# Cyusb3014_-_3.net
KiCad netlist of a schematic drawn in Altium Designer
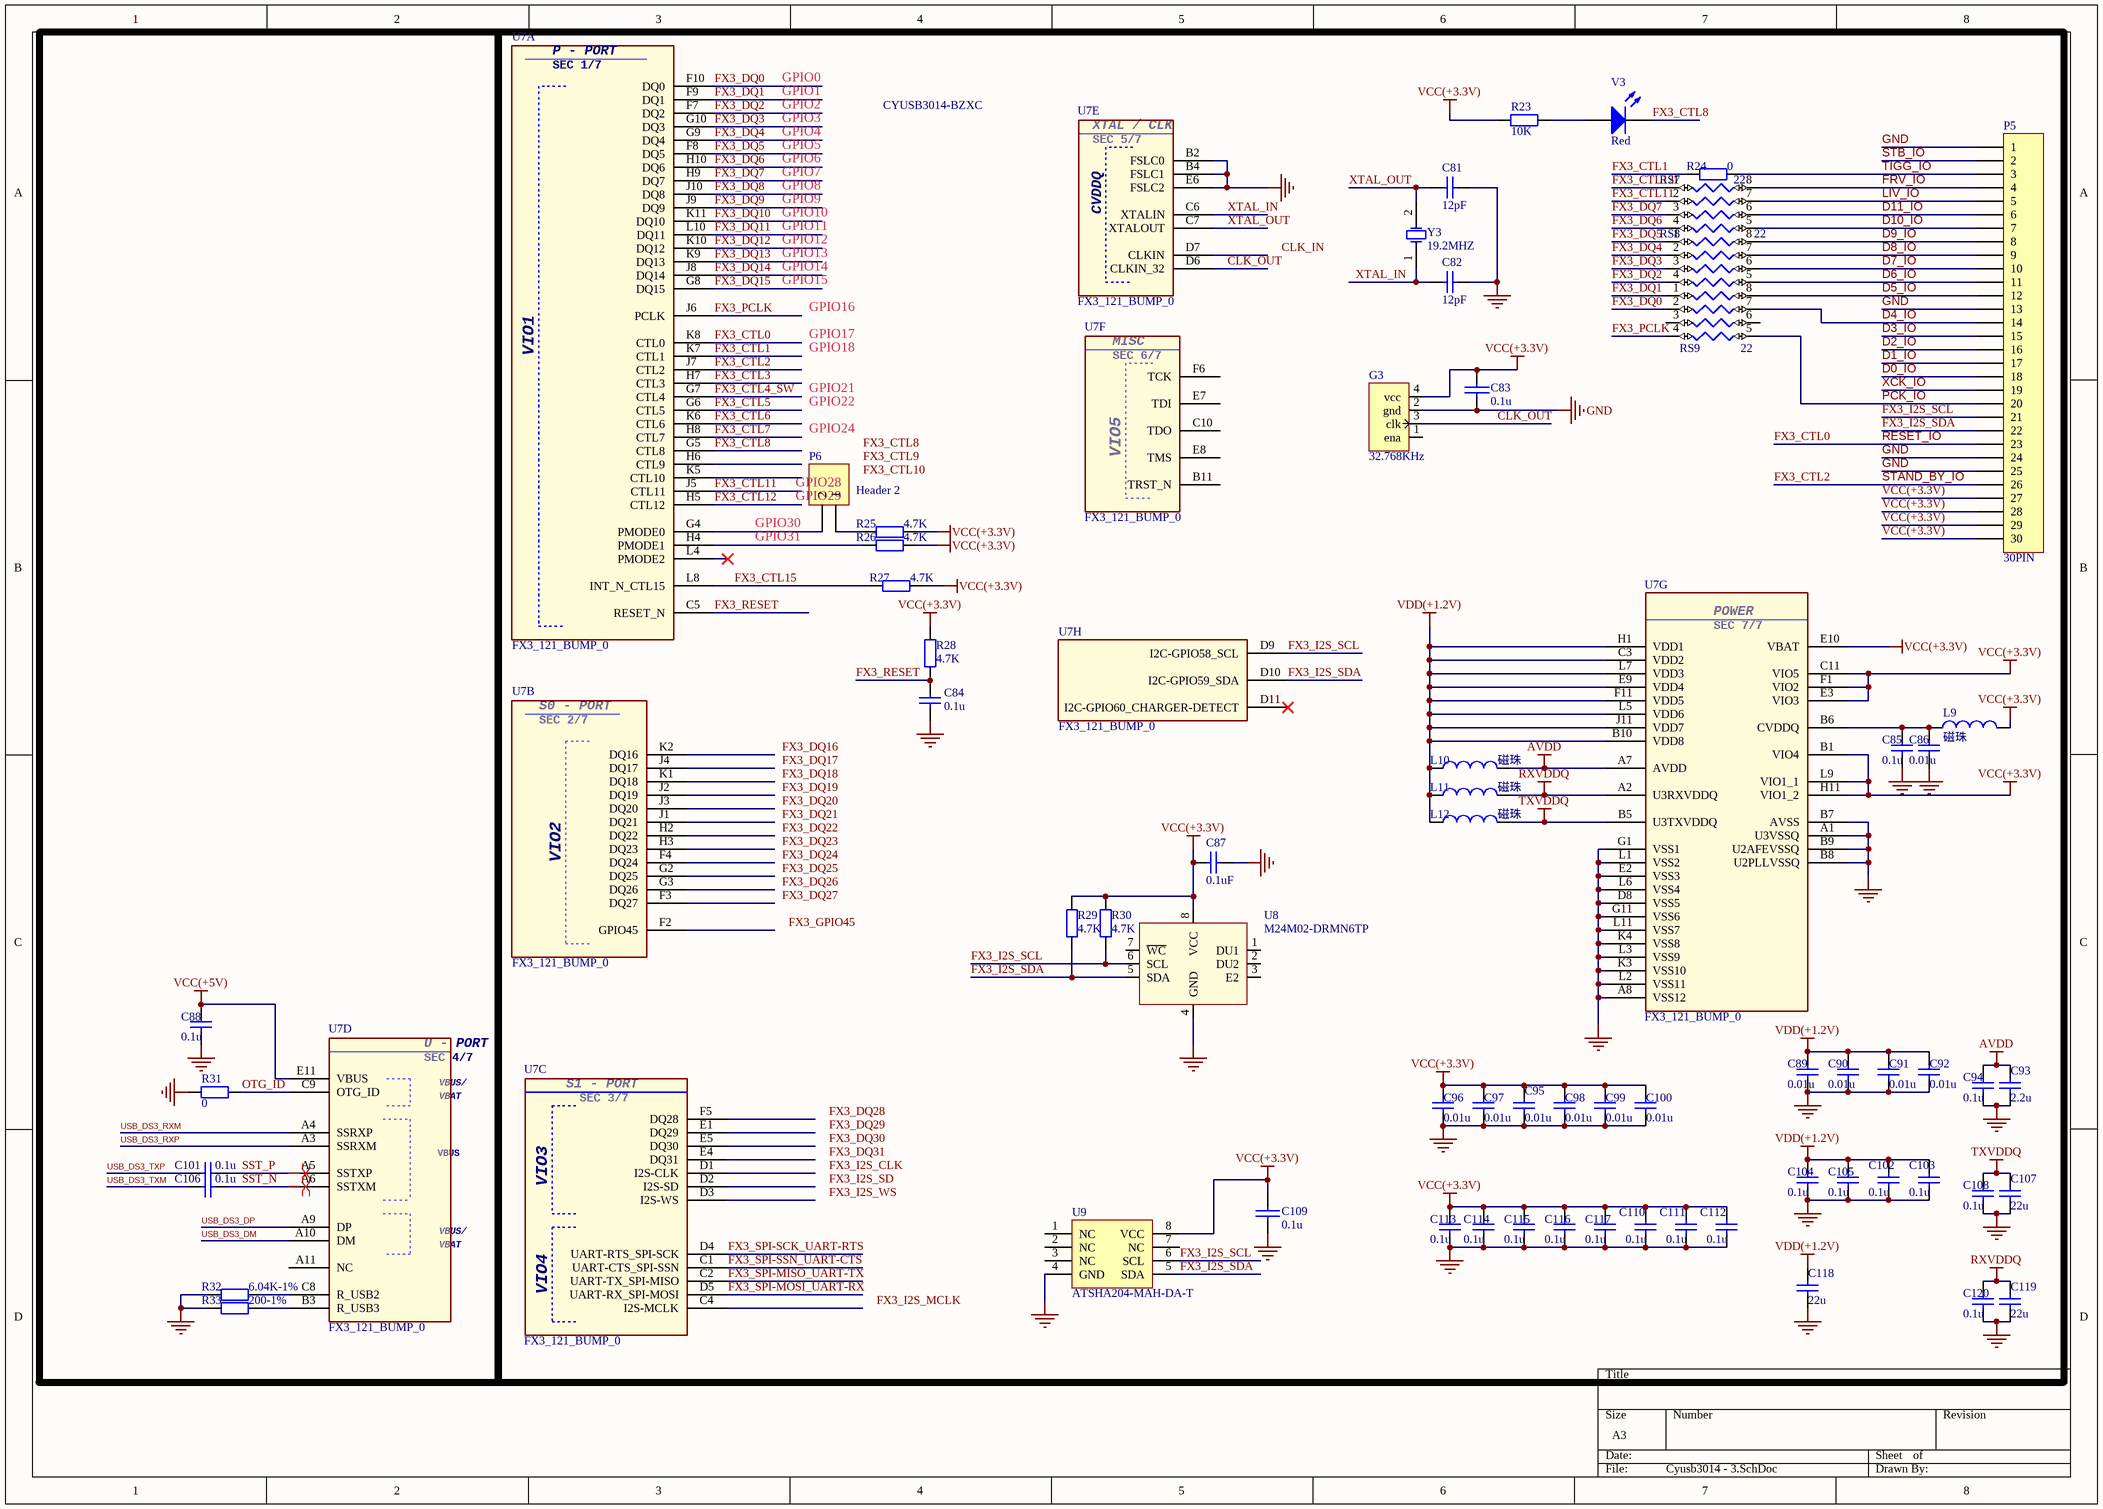
[diagram p0: Cyusb3014 - 3.SchDoc]

(export (version "E")
  (design (tool "Eeschema 10.0.6"))
  (components
    (comp (ref "C81")
      (value "12pF")
      (footprint "0603S-CAP")
      (description "CAP CER SMT 4.3pF 0805")
      (fields
        (field (name "2. MANUFACTURERE PART NUMBER") "C0805C439D5GACTU")
        (field (name "8. ALTERNATE PART") "any")
      )
      (libsource (lib "Peeple_eval") (part "CAP CER SMT 4.3pF 0805"))
    )
    (comp (ref "C82")
      (value "12pF")
      (footprint "0603S-CAP")
      (description "CAP CER SMT 4.3pF 0805")
      (fields
        (field (name "2. MANUFACTURERE PART NUMBER") "C0805C439D5GACTU")
        (field (name "8. ALTERNATE PART") "any")
      )
      (libsource (lib "Peeple_eval") (part "CAP CER SMT 4.3pF 0805"))
    )
    (comp (ref "C83")
      (value "0.1u")
      (footprint "0603S-CAP")
      (description "RC=1206")
      (libsource (lib "*") (part "CAP"))
    )
    (comp (ref "C84")
      (value "0.1u")
      (footprint "0603S-CAP")
      (description "50V/8.2u/0805")
      (fields (field (name "PUBLISHER") "Altium Limited"))
      (libsource (lib "Miscellaneous Devices") (part "Cap"))
    )
    (comp (ref "C85")
      (value "0.1u")
      (footprint "C0402")
      (description "Capacitor")
      (fields (field (name "PUBLISHER") "Altium Limited"))
      (libsource (lib "WM360") (part "CAP0805"))
    )
    (comp (ref "C86")
      (value "0.01u")
      (footprint "C0402")
      (description "Capacitor")
      (fields (field (name "PUBLISHER") "Altium Limited"))
      (libsource (lib "WM360") (part "CAP0805"))
    )
    (comp (ref "C87")
      (value "0.1uF")
      (footprint "0603S-CAP")
      (description "CAP SMT 0.1uF 16V X7R")
      (fields
        (field (name "2. MANUFACTURERE PART NUMBER") "C0805C104K4RACTU")
        (field (name "8. ALTERNATE PART") "any")
      )
      (libsource (lib "Peeple_eval") (part "CAP SMT 0.1uF 16V X7R"))
    )
    (comp (ref "C88")
      (value "0.1u")
      (footprint "C0402")
      (description "Capacitor")
      (fields (field (name "PUBLISHER") "Altium Limited"))
      (libsource (lib "WM360") (part "CAP0805"))
    )
    (comp (ref "C89")
      (value "0.01u")
      (footprint "C0402")
      (description "Capacitor")
      (fields (field (name "PUBLISHER") "Altium Limited"))
      (libsource (lib "WM360") (part "CAP0805"))
    )
    (comp (ref "C90")
      (value "0.01u")
      (footprint "C0402")
      (description "Capacitor")
      (fields (field (name "PUBLISHER") "Altium Limited"))
      (libsource (lib "WM360") (part "CAP0805"))
    )
    (comp (ref "C91")
      (value "0.01u")
      (footprint "C0402")
      (description "Capacitor")
      (fields (field (name "PUBLISHER") "Altium Limited"))
      (libsource (lib "WM360") (part "CAP0805"))
    )
    (comp (ref "C92")
      (value "0.01u")
      (footprint "C0402")
      (description "Capacitor")
      (fields (field (name "PUBLISHER") "Altium Limited"))
      (libsource (lib "WM360") (part "CAP0805"))
    )
    (comp (ref "C93")
      (value "2.2u")
      (footprint "C0805S-CAP")
      (description "Capacitor")
      (fields (field (name "PUBLISHER") "Altium Limited"))
      (libsource (lib "USB_CAMERA") (part "CAP0805"))
    )
    (comp (ref "C94")
      (value "0.1u")
      (footprint "C0402")
      (description "Capacitor")
      (fields (field (name "PUBLISHER") "Altium Limited"))
      (libsource (lib "WM360") (part "CAP0805"))
    )
    (comp (ref "C95")
      (value "0.01u")
      (footprint "C0402")
      (description "Capacitor")
      (fields (field (name "PUBLISHER") "Altium Limited"))
      (libsource (lib "WM360") (part "CAP0805"))
    )
    (comp (ref "C96")
      (value "0.01u")
      (footprint "C0402")
      (description "Capacitor")
      (fields (field (name "PUBLISHER") "Altium Limited"))
      (libsource (lib "WM360") (part "CAP0805"))
    )
    (comp (ref "C97")
      (value "0.01u")
      (footprint "C0402")
      (description "Capacitor")
      (fields (field (name "PUBLISHER") "Altium Limited"))
      (libsource (lib "WM360") (part "CAP0805"))
    )
    (comp (ref "C98")
      (value "0.01u")
      (footprint "C0402")
      (description "Capacitor")
      (fields (field (name "PUBLISHER") "Altium Limited"))
      (libsource (lib "WM360") (part "CAP0805"))
    )
    (comp (ref "C99")
      (value "0.01u")
      (footprint "C0402")
      (description "Capacitor")
      (fields (field (name "PUBLISHER") "Altium Limited"))
      (libsource (lib "WM360") (part "CAP0805"))
    )
    (comp (ref "C100")
      (value "0.01u")
      (footprint "C0402")
      (description "Capacitor")
      (fields (field (name "PUBLISHER") "Altium Limited"))
      (libsource (lib "WM360") (part "CAP0805"))
    )
    (comp (ref "C101")
      (value "0.1u")
      (footprint "C0402")
      (description "Capacitor")
      (fields (field (name "PUBLISHER") "Altium Limited"))
      (libsource (lib "WM360") (part "CAP0805"))
    )
    (comp (ref "C102")
      (value "0.1u")
      (footprint "C0402")
      (description "Capacitor")
      (fields (field (name "PUBLISHER") "Altium Limited"))
      (libsource (lib "WM360") (part "CAP0805"))
    )
    (comp (ref "C103")
      (value "0.1u")
      (footprint "C0402")
      (description "Capacitor")
      (fields (field (name "PUBLISHER") "Altium Limited"))
      (libsource (lib "WM360") (part "CAP0805"))
    )
    (comp (ref "C104")
      (value "0.1u")
      (footprint "C0402")
      (description "Capacitor")
      (fields (field (name "PUBLISHER") "Altium Limited"))
      (libsource (lib "WM360") (part "CAP0805"))
    )
    (comp (ref "C105")
      (value "0.1u")
      (footprint "C0402")
      (description "Capacitor")
      (fields (field (name "PUBLISHER") "Altium Limited"))
      (libsource (lib "WM360") (part "CAP0805"))
    )
    (comp (ref "C106")
      (value "0.1u")
      (footprint "C0402")
      (description "Capacitor")
      (fields (field (name "PUBLISHER") "Altium Limited"))
      (libsource (lib "WM360") (part "CAP0805"))
    )
    (comp (ref "C107")
      (value "22u")
      (footprint "C0805S-CAP")
      (description "Capacitor")
      (fields (field (name "PUBLISHER") "Altium Limited"))
      (libsource (lib "USB_CAMERA") (part "CAP0805"))
    )
    (comp (ref "C108")
      (value "0.1u")
      (footprint "C0402")
      (description "Capacitor")
      (fields (field (name "PUBLISHER") "Altium Limited"))
      (libsource (lib "WM360") (part "CAP0805"))
    )
    (comp (ref "C109")
      (value "0.1u")
      (footprint "0603S-CAP")
      (description "RC=1206")
      (libsource (lib "*") (part "CAP"))
    )
    (comp (ref "C110")
      (value "0.1u")
      (footprint "C0402")
      (description "Capacitor")
      (fields (field (name "PUBLISHER") "Altium Limited"))
      (libsource (lib "WM360") (part "CAP0805"))
    )
    (comp (ref "C111")
      (value "0.1u")
      (footprint "C0402")
      (description "Capacitor")
      (fields (field (name "PUBLISHER") "Altium Limited"))
      (libsource (lib "WM360") (part "CAP0805"))
    )
    (comp (ref "C112")
      (value "0.1u")
      (footprint "C0402")
      (description "Capacitor")
      (fields (field (name "PUBLISHER") "Altium Limited"))
      (libsource (lib "WM360") (part "CAP0805"))
    )
    (comp (ref "C113")
      (value "0.1u")
      (footprint "C0402")
      (description "Capacitor")
      (fields (field (name "PUBLISHER") "Altium Limited"))
      (libsource (lib "WM360") (part "CAP0805"))
    )
    (comp (ref "C114")
      (value "0.1u")
      (footprint "C0402")
      (description "Capacitor")
      (fields (field (name "PUBLISHER") "Altium Limited"))
      (libsource (lib "WM360") (part "CAP0805"))
    )
    (comp (ref "C115")
      (value "0.1u")
      (footprint "C0402")
      (description "Capacitor")
      (fields (field (name "PUBLISHER") "Altium Limited"))
      (libsource (lib "WM360") (part "CAP0805"))
    )
    (comp (ref "C116")
      (value "0.1u")
      (footprint "C0402")
      (description "Capacitor")
      (fields (field (name "PUBLISHER") "Altium Limited"))
      (libsource (lib "WM360") (part "CAP0805"))
    )
    (comp (ref "C117")
      (value "0.1u")
      (footprint "C0402")
      (description "Capacitor")
      (fields (field (name "PUBLISHER") "Altium Limited"))
      (libsource (lib "WM360") (part "CAP0805"))
    )
    (comp (ref "C118")
      (value "22u")
      (footprint "C0805S-CAP")
      (description "Capacitor")
      (fields (field (name "PUBLISHER") "Altium Limited"))
      (libsource (lib "USB_CAMERA") (part "CAP0805"))
    )
    (comp (ref "C119")
      (value "22u")
      (footprint "C0805S-CAP")
      (description "Capacitor")
      (fields (field (name "PUBLISHER") "Altium Limited"))
      (libsource (lib "USB_CAMERA") (part "CAP0805"))
    )
    (comp (ref "C120")
      (value "0.1u")
      (footprint "C0402")
      (description "Capacitor")
      (fields (field (name "PUBLISHER") "Altium Limited"))
      (libsource (lib "WM360") (part "CAP0805"))
    )
    (comp (ref "G3") (value "32.768KHz") (footprint "爱普生晶振3.2×2.5mm") (libsource (lib "*") (part "CTY4-B")))
    (comp (ref "L9")
      (value "磁珠")
      (footprint "L0603")
      (description "Inductor")
      (fields (field (name "PUBLISHER") "Altium Limited"))
      (libsource (lib "Miscellaneous Devices") (part "Inductor"))
    )
    (comp (ref "L10")
      (value "磁珠")
      (footprint "L0603")
      (description "Inductor")
      (fields (field (name "PUBLISHER") "Altium Limited"))
      (libsource (lib "Miscellaneous Devices") (part "Inductor"))
    )
    (comp (ref "L11")
      (value "磁珠")
      (footprint "L0603")
      (description "Inductor")
      (fields (field (name "PUBLISHER") "Altium Limited"))
      (libsource (lib "Miscellaneous Devices") (part "Inductor"))
    )
    (comp (ref "L12")
      (value "磁珠")
      (footprint "L0603")
      (description "Inductor")
      (fields (field (name "PUBLISHER") "Altium Limited"))
      (libsource (lib "Miscellaneous Devices") (part "Inductor"))
    )
    (comp (ref "P5")
      (value "30PIN")
      (footprint "FH12-30S-0.5SH")
      (description "Header, 30-Pin")
      (fields (field (name "PUBLISHER") "Altium Limited"))
      (libsource (lib "Miscellaneous Connectors") (part "Header 30"))
    )
    (comp (ref "P6")
      (value "Header 2")
      (footprint "HDR1X2")
      (description "Header, 2-Pin")
      (fields (field (name "PUBLISHER") "Altium Limited"))
      (libsource (lib "Miscellaneous Connectors") (part "Header 2"))
    )
    (comp (ref "R23")
      (value "10K")
      (footprint "0603S-RES")
      (description "Resistor")
      (fields (field (name "PUBLISHER") "Altium Limited"))
      (libsource (lib "") (part "Res2_2"))
    )
    (comp (ref "R24")
      (value "0")
      (footprint "0603S-RES")
      (description "Resistor")
      (fields (field (name "PUBLISHER") "Altium Limited"))
      (libsource (lib "") (part "Res2_2"))
    )
    (comp (ref "R25")
      (value "4.7K")
      (footprint "0603S-RES")
      (description "Resistor")
      (fields (field (name "PUBLISHER") "Altium Limited"))
      (libsource (lib "DM642") (part "Res2"))
    )
    (comp (ref "R26")
      (value "4.7K")
      (footprint "0603S-RES")
      (description "Resistor")
      (fields (field (name "PUBLISHER") "Altium Limited"))
      (libsource (lib "DM642") (part "Res2"))
    )
    (comp (ref "R27")
      (value "4.7K")
      (footprint "0603S-RES")
      (description "Resistor")
      (fields (field (name "PUBLISHER") "Altium Limited"))
      (libsource (lib "") (part "Res2_1"))
    )
    (comp (ref "R28")
      (value "4.7K")
      (footprint "0603S-RES")
      (description "Resistor")
      (fields (field (name "PUBLISHER") "Altium Limited"))
      (libsource (lib "") (part "Res2_3"))
    )
    (comp (ref "R29")
      (value "4.7K")
      (footprint "0603S-RES")
      (description "Resistor")
      (fields (field (name "PUBLISHER") "Altium Limited"))
      (libsource (lib "DM642") (part "Res2"))
    )
    (comp (ref "R30")
      (value "4.7K")
      (footprint "0603S-RES")
      (description "Resistor")
      (fields (field (name "PUBLISHER") "Altium Limited"))
      (libsource (lib "DM642") (part "Res2"))
    )
    (comp (ref "R31")
      (value "0")
      (footprint "0603S-RES")
      (description "Resistor")
      (fields (field (name "PUBLISHER") "Altium Limited"))
      (libsource (lib "") (part "Res2_1"))
    )
    (comp (ref "R32")
      (value "6.04K-1%")
      (footprint "0603S-RES")
      (description "Resistor")
      (fields (field (name "PUBLISHER") "Altium Limited"))
      (libsource (lib "") (part "Res2_1"))
    )
    (comp (ref "R33")
      (value "200-1%")
      (footprint "0603S-RES")
      (description "Resistor")
      (fields (field (name "PUBLISHER") "Altium Limited"))
      (libsource (lib "") (part "Res2_1"))
    )
    (comp (ref "RS7") (value "22") (footprint "NC06-4") (libsource (lib "*") (part "RN4")))
    (comp (ref "RS8") (value "22") (footprint "NC06-4") (libsource (lib "*") (part "RN4")))
    (comp (ref "RS9") (value "22") (footprint "NC06-4") (libsource (lib "*") (part "RN4")))
    (comp (ref "U7")
      (value "FX3_121_BUMP_0")
      (footprint "121_BGA_FX3")
      (libsource (lib "USB_CAMERA") (part "FX3_121_BUMP_0"))
    )
    (comp (ref "U8")
      (value "M24M02-DRMN6TP")
      (footprint "SOIC127P600X175-8N")
      (description "IC EEPROM 64KBIT 400KHZ 8SOIC")
      (fields
        (field (name "MANUFACTURER") "Microchip Technology")
        (field (name "MANUFACTURER PART NUMBER") "24LC64-I/SN")
      )
      (libsource (lib "Schlib1") (part "24LC64-I/SN"))
    )
    (comp (ref "U9")
      (value "ATSHA204-MAH-DA-T")
      (footprint "UDFN")
      (libsource (lib "CY7C68013-56") (part "AT24C128"))
    )
    (comp (ref "V3")
      (value "Red")
      (footprint "LED0805S")
      (description "Typical INFRARED GaAs LED")
      (fields (field (name "PUBLISHER") "Altium Limited"))
      (libsource (lib "DM642") (part "LED0"))
    )
    (comp (ref "Y3")
      (value "19.2MHZ")
      (footprint "爱普生晶振3.2×2.5MM - 无源")
      (description "Crystal, CRYSTAL 32.768KHZ 6PF SMD")
      (fields
        (field (name "2. MANUFACTURERE PART NUMBER") "ABS07-120-32.768KHZ-T")
        (field (name "4. SUPPLIER PART NUMBER") "535-11937-1-ND")
      )
      (libsource (lib "Peeple_eval") (part "XTAL 32.768KHZ"))
    )
  )
  (nets
    (net (code "2") (name "/CLK_OUT") (class "Default")
      (node (ref "G3") (pin "3") (pinfunction "clk_3") (pintype "passive"))
      (node (ref "U7") (pin "D6") (pinfunction "CLKIN_32_D6") (pintype "passive"))
    )
    (net (code "3") (name "/D0_IO") (class "Default")
      (node (ref "P5") (pin "18") (pinfunction "18_18") (pintype "passive"))
    )
    (net (code "4") (name "/D1_IO") (class "Default")
      (node (ref "P5") (pin "17") (pinfunction "17_17") (pintype "passive"))
    )
    (net (code "5") (name "/D2_IO") (class "Default")
      (node (ref "P5") (pin "16") (pinfunction "16_16") (pintype "passive"))
    )
    (net (code "6") (name "/D3_IO") (class "Default")
      (node (ref "P5") (pin "15") (pinfunction "15_15") (pintype "passive"))
    )
    (net (code "7") (name "/D4_IO") (class "Default")
      (node (ref "P5") (pin "14") (pinfunction "14_14") (pintype "passive"))
      (node (ref "RS9") (pin "7") (pinfunction "7_7") (pintype "bidirectional"))
    )
    (net (code "8") (name "/D5_IO") (class "Default")
      (node (ref "P5") (pin "12") (pinfunction "12_12") (pintype "passive"))
      (node (ref "RS9") (pin "8") (pinfunction "8_8") (pintype "bidirectional"))
    )
    (net (code "9") (name "/D6_IO") (class "Default")
      (node (ref "P5") (pin "11") (pinfunction "11_11") (pintype "passive"))
      (node (ref "RS8") (pin "5") (pinfunction "5_5") (pintype "bidirectional"))
    )
    (net (code "10") (name "/D7_IO") (class "Default")
      (node (ref "P5") (pin "10") (pinfunction "10_10") (pintype "passive"))
      (node (ref "RS8") (pin "6") (pinfunction "6_6") (pintype "bidirectional"))
    )
    (net (code "11") (name "/D8_IO") (class "Default")
      (node (ref "P5") (pin "9") (pinfunction "9_9") (pintype "passive"))
      (node (ref "RS8") (pin "7") (pinfunction "7_7") (pintype "bidirectional"))
    )
    (net (code "12") (name "/D9_IO") (class "Default")
      (node (ref "P5") (pin "8") (pinfunction "8_8") (pintype "passive"))
      (node (ref "RS8") (pin "8") (pinfunction "8_8") (pintype "bidirectional"))
    )
    (net (code "13") (name "/D10_IO") (class "Default")
      (node (ref "P5") (pin "7") (pinfunction "7_7") (pintype "passive"))
      (node (ref "RS7") (pin "5") (pinfunction "5_5") (pintype "bidirectional"))
    )
    (net (code "14") (name "/D11_IO") (class "Default")
      (node (ref "P5") (pin "6") (pinfunction "6_6") (pintype "passive"))
      (node (ref "RS7") (pin "6") (pinfunction "6_6") (pintype "bidirectional"))
    )
    (net (code "15") (name "/FRV_IO") (class "Default")
      (node (ref "P5") (pin "4") (pinfunction "4_4") (pintype "passive"))
      (node (ref "RS7") (pin "8") (pinfunction "8_8") (pintype "bidirectional"))
    )
    (net (code "16") (name "/FX3_CTL0") (class "Default")
      (node (ref "P5") (pin "23") (pinfunction "23_23") (pintype "passive"))
      (node (ref "U7") (pin "K8") (pinfunction "CTL0_K8") (pintype "passive"))
    )
    (net (code "17") (name "/FX3_CTL1") (class "Default")
      (node (ref "R24") (pin "2") (pinfunction "2_2") (pintype "passive"))
      (node (ref "U7") (pin "K7") (pinfunction "CTL1_K7") (pintype "passive"))
    )
    (net (code "18") (name "/FX3_CTL2") (class "Default")
      (node (ref "P5") (pin "26") (pinfunction "26_26") (pintype "passive"))
      (node (ref "U7") (pin "J7") (pinfunction "CTL2_J7") (pintype "passive"))
    )
    (net (code "19") (name "/FX3_CTL3") (class "Default")
      (node (ref "U7") (pin "H7") (pinfunction "CTL3_H7") (pintype "passive"))
    )
    (net (code "20") (name "/FX3_CTL4_SW") (class "Default")
      (node (ref "U7") (pin "G7") (pinfunction "CTL4_G7") (pintype "passive"))
    )
    (net (code "21") (name "/FX3_CTL5") (class "Default")
      (node (ref "U7") (pin "G6") (pinfunction "CTL5_G6") (pintype "passive"))
    )
    (net (code "22") (name "/FX3_CTL6") (class "Default")
      (node (ref "U7") (pin "K6") (pinfunction "CTL6_K6") (pintype "passive"))
    )
    (net (code "23") (name "/FX3_CTL7") (class "Default")
      (node (ref "U7") (pin "H8") (pinfunction "CTL7_H8") (pintype "passive"))
    )
    (net (code "24") (name "/FX3_CTL8") (class "Default")
      (node (ref "U7") (pin "G5") (pinfunction "CTL8_G5") (pintype "passive"))
      (node (ref "V3") (pin "2") (pinfunction "K_2") (pintype "passive"))
    )
    (net (code "27") (name "/FX3_CTL11") (class "Default")
      (node (ref "RS7") (pin "2") (pinfunction "2_2") (pintype "bidirectional"))
      (node (ref "U7") (pin "J5") (pinfunction "CTL11_J5") (pintype "passive"))
    )
    (net (code "28") (name "/FX3_CTL12") (class "Default")
      (node (ref "RS7") (pin "1") (pinfunction "1_1") (pintype "bidirectional"))
      (node (ref "U7") (pin "H5") (pinfunction "CTL12_H5") (pintype "passive"))
    )
    (net (code "29") (name "/FX3_CTL15") (class "Default")
      (node (ref "R27") (pin "2") (pinfunction "2_2") (pintype "passive"))
      (node (ref "U7") (pin "L8") (pinfunction "INT_N_CTL15_L8") (pintype "passive"))
    )
    (net (code "30") (name "/FX3_DQ0") (class "Default")
      (node (ref "RS9") (pin "2") (pinfunction "2_2") (pintype "bidirectional"))
      (node (ref "U7") (pin "F10") (pinfunction "DQ0_F10") (pintype "passive"))
    )
    (net (code "31") (name "/FX3_DQ1") (class "Default")
      (node (ref "RS9") (pin "1") (pinfunction "1_1") (pintype "bidirectional"))
      (node (ref "U7") (pin "F9") (pinfunction "DQ1_F9") (pintype "passive"))
    )
    (net (code "32") (name "/FX3_DQ2") (class "Default")
      (node (ref "RS8") (pin "4") (pinfunction "4_4") (pintype "bidirectional"))
      (node (ref "U7") (pin "F7") (pinfunction "DQ2_F7") (pintype "passive"))
    )
    (net (code "33") (name "/FX3_DQ3") (class "Default")
      (node (ref "RS8") (pin "3") (pinfunction "3_3") (pintype "bidirectional"))
      (node (ref "U7") (pin "G10") (pinfunction "DQ3_G10") (pintype "passive"))
    )
    (net (code "34") (name "/FX3_DQ4") (class "Default")
      (node (ref "RS8") (pin "2") (pinfunction "2_2") (pintype "bidirectional"))
      (node (ref "U7") (pin "G9") (pinfunction "DQ4_G9") (pintype "passive"))
    )
    (net (code "35") (name "/FX3_DQ5") (class "Default")
      (node (ref "RS8") (pin "1") (pinfunction "1_1") (pintype "bidirectional"))
      (node (ref "U7") (pin "F8") (pinfunction "DQ5_F8") (pintype "passive"))
    )
    (net (code "36") (name "/FX3_DQ6") (class "Default")
      (node (ref "RS7") (pin "4") (pinfunction "4_4") (pintype "bidirectional"))
      (node (ref "U7") (pin "H10") (pinfunction "DQ6_H10") (pintype "passive"))
    )
    (net (code "37") (name "/FX3_DQ7") (class "Default")
      (node (ref "RS7") (pin "3") (pinfunction "3_3") (pintype "bidirectional"))
      (node (ref "U7") (pin "H9") (pinfunction "DQ7_H9") (pintype "passive"))
    )
    (net (code "38") (name "/FX3_DQ8") (class "Default")
      (node (ref "U7") (pin "J10") (pinfunction "DQ8_J10") (pintype "passive"))
    )
    (net (code "39") (name "/FX3_DQ9") (class "Default")
      (node (ref "U7") (pin "J9") (pinfunction "DQ9_J9") (pintype "passive"))
    )
    (net (code "40") (name "/FX3_DQ10") (class "Default")
      (node (ref "U7") (pin "K11") (pinfunction "DQ10_K11") (pintype "passive"))
    )
    (net (code "41") (name "/FX3_DQ11") (class "Default")
      (node (ref "U7") (pin "L10") (pinfunction "DQ11_L10") (pintype "passive"))
    )
    (net (code "42") (name "/FX3_DQ12") (class "Default")
      (node (ref "U7") (pin "K10") (pinfunction "DQ12_K10") (pintype "passive"))
    )
    (net (code "43") (name "/FX3_DQ13") (class "Default")
      (node (ref "U7") (pin "K9") (pinfunction "DQ13_K9") (pintype "passive"))
    )
    (net (code "44") (name "/FX3_DQ14") (class "Default")
      (node (ref "U7") (pin "J8") (pinfunction "DQ14_J8") (pintype "passive"))
    )
    (net (code "45") (name "/FX3_DQ15") (class "Default")
      (node (ref "U7") (pin "G8") (pinfunction "DQ15_G8") (pintype "passive"))
    )
    (net (code "65") (name "/FX3_I2S_SCL") (class "Default")
      (node (ref "P5") (pin "21") (pinfunction "21_21") (pintype "passive"))
      (node (ref "R30") (pin "1") (pinfunction "1_1") (pintype "passive"))
      (node (ref "U7") (pin "D9") (pinfunction "I2C-GPIO58_SCL_D9") (pintype "passive"))
      (node (ref "U8") (pin "6") (pinfunction "SCL_6") (pintype "passive"))
      (node (ref "U9") (pin "6") (pinfunction "SCL_6") (pintype "passive"))
    )
    (net (code "67") (name "/FX3_I2S_SDA") (class "Default")
      (node (ref "P5") (pin "22") (pinfunction "22_22") (pintype "passive"))
      (node (ref "R29") (pin "1") (pinfunction "1_1") (pintype "passive"))
      (node (ref "U7") (pin "D10") (pinfunction "I2C-GPIO59_SDA_D10") (pintype "passive"))
      (node (ref "U8") (pin "5") (pinfunction "SDA_5") (pintype "passive"))
      (node (ref "U9") (pin "5") (pinfunction "SDA_5") (pintype "passive"))
    )
    (net (code "69") (name "/FX3_PCLK") (class "Default")
      (node (ref "RS9") (pin "4") (pinfunction "4_4") (pintype "bidirectional"))
      (node (ref "U7") (pin "J6") (pinfunction "PCLK_J6") (pintype "passive"))
    )
    (net (code "70") (name "/FX3_RESET") (class "Default")
      (node (ref "C84") (pin "2") (pinfunction "2_2") (pintype "passive"))
      (node (ref "R28") (pin "2") (pinfunction "2_2") (pintype "passive"))
      (node (ref "U7") (pin "C5") (pinfunction "RESET_N_C5") (pintype "passive"))
    )
    (net (code "71") (name "/FX3_SPI-MISO_UART-TX") (class "Default")
      (node (ref "U7") (pin "C2") (pinfunction "UART-TX_SPI-MISO_C2") (pintype "passive"))
    )
    (net (code "72") (name "/FX3_SPI-MOSI_UART-RX") (class "Default")
      (node (ref "U7") (pin "D5") (pinfunction "UART-RX_SPI-MOSI_D5") (pintype "passive"))
    )
    (net (code "73") (name "/FX3_SPI-SCK_UART-RTS") (class "Default")
      (node (ref "U7") (pin "D4") (pinfunction "UART-RTS_SPI-SCK_D4") (pintype "passive"))
    )
    (net (code "74") (name "/FX3_SPI-SSN_UART-CTS") (class "Default")
      (node (ref "U7") (pin "C1") (pinfunction "UART-CTS_SPI-SSN_C1") (pintype "passive"))
    )
    (net (code "75") (name "/LIV_IO") (class "Default")
      (node (ref "P5") (pin "5") (pinfunction "5_5") (pintype "passive"))
      (node (ref "RS7") (pin "7") (pinfunction "7_7") (pintype "bidirectional"))
    )
    (net (code "76") (name "/OTG_ID") (class "Default")
      (node (ref "R31") (pin "1") (pinfunction "1_1") (pintype "passive"))
      (node (ref "U7") (pin "C9") (pinfunction "OTG_ID_C9") (pintype "passive"))
    )
    (net (code "77") (name "/PCK_IO") (class "Default")
      (node (ref "P5") (pin "20") (pinfunction "20_20") (pintype "passive"))
      (node (ref "RS9") (pin "5") (pinfunction "5_5") (pintype "bidirectional"))
    )
    (net (code "78") (name "/SST_N") (class "Default")
      (node (ref "C106") (pin "2") (pinfunction "2_2") (pintype "passive"))
      (node (ref "U7") (pin "A6") (pinfunction "SSTXM_A6") (pintype "passive"))
    )
    (net (code "79") (name "/SST_P") (class "Default")
      (node (ref "C101") (pin "2") (pinfunction "2_2") (pintype "passive"))
      (node (ref "U7") (pin "A5") (pinfunction "SSTXP_A5") (pintype "passive"))
    )
    (net (code "80") (name "/STB_IO") (class "Default")
      (node (ref "P5") (pin "2") (pinfunction "2_2") (pintype "passive"))
    )
    (net (code "81") (name "/TIGG_IO") (class "Default")
      (node (ref "P5") (pin "3") (pinfunction "3_3") (pintype "passive"))
      (node (ref "R24") (pin "1") (pinfunction "1_1") (pintype "passive"))
    )
    (net (code "82") (name "/USB_DS3_DM") (class "Default")
      (node (ref "U7") (pin "A10") (pinfunction "DM_A10") (pintype "passive"))
    )
    (net (code "83") (name "/USB_DS3_DP") (class "Default")
      (node (ref "U7") (pin "A9") (pinfunction "DP_A9") (pintype "passive"))
    )
    (net (code "84") (name "/USB_DS3_RXM") (class "Default")
      (node (ref "U7") (pin "A4") (pinfunction "SSRXP_A4") (pintype "passive"))
    )
    (net (code "85") (name "/USB_DS3_RXP") (class "Default")
      (node (ref "U7") (pin "A3") (pinfunction "SSRXM_A3") (pintype "passive"))
    )
    (net (code "86") (name "/USB_DS3_TXM") (class "Default")
      (node (ref "C106") (pin "1") (pinfunction "1_1") (pintype "passive"))
    )
    (net (code "87") (name "/USB_DS3_TXP") (class "Default")
      (node (ref "C101") (pin "1") (pinfunction "1_1") (pintype "passive"))
    )
    (net (code "88") (name "/XCK_IO") (class "Default")
      (node (ref "P5") (pin "19") (pinfunction "19_19") (pintype "passive"))
    )
    (net (code "89") (name "/XTAL_IN") (class "Default")
      (node (ref "C82") (pin "2") (pinfunction "2_2") (pintype "passive"))
      (node (ref "U7") (pin "C6") (pinfunction "XTALIN_C6") (pintype "passive"))
      (node (ref "Y3") (pin "1") (pinfunction "OSC1_1") (pintype "passive"))
    )
    (net (code "90") (name "/XTAL_OUT") (class "Default")
      (node (ref "C81") (pin "2") (pinfunction "2_2") (pintype "passive"))
      (node (ref "U7") (pin "C7") (pinfunction "XTALOUT_C7") (pintype "passive"))
      (node (ref "Y3") (pin "2") (pinfunction "OSC2_2") (pintype "passive"))
    )
    (net (code "91") (name "AVDD") (class "Default")
      (node (ref "C93") (pin "2") (pinfunction "2_2") (pintype "passive"))
      (node (ref "C94") (pin "1") (pinfunction "1_1") (pintype "passive"))
      (node (ref "L10") (pin "2") (pinfunction "2_2") (pintype "passive"))
      (node (ref "U7") (pin "A7") (pinfunction "AVDD_A7") (pintype "passive"))
    )
    (net (code "92") (name "GND") (class "Default")
      (node (ref "C100") (pin "2") (pinfunction "2_2") (pintype "passive"))
      (node (ref "C102") (pin "2") (pinfunction "2_2") (pintype "passive"))
      (node (ref "C103") (pin "2") (pinfunction "2_2") (pintype "passive"))
      (node (ref "C104") (pin "2") (pinfunction "2_2") (pintype "passive"))
      (node (ref "C105") (pin "2") (pinfunction "2_2") (pintype "passive"))
      (node (ref "C107") (pin "1") (pinfunction "1_1") (pintype "passive"))
      (node (ref "C108") (pin "2") (pinfunction "2_2") (pintype "passive"))
      (node (ref "C109") (pin "2") (pintype "passive"))
      (node (ref "C110") (pin "2") (pinfunction "2_2") (pintype "passive"))
      (node (ref "C111") (pin "2") (pinfunction "2_2") (pintype "passive"))
      (node (ref "C112") (pin "2") (pinfunction "2_2") (pintype "passive"))
      (node (ref "C113") (pin "2") (pinfunction "2_2") (pintype "passive"))
      (node (ref "C114") (pin "2") (pinfunction "2_2") (pintype "passive"))
      (node (ref "C115") (pin "2") (pinfunction "2_2") (pintype "passive"))
      (node (ref "C116") (pin "2") (pinfunction "2_2") (pintype "passive"))
      (node (ref "C117") (pin "2") (pinfunction "2_2") (pintype "passive"))
      (node (ref "C118") (pin "1") (pinfunction "1_1") (pintype "passive"))
      (node (ref "C119") (pin "1") (pinfunction "1_1") (pintype "passive"))
      (node (ref "C120") (pin "2") (pinfunction "2_2") (pintype "passive"))
      (node (ref "C81") (pin "1") (pinfunction "1_1") (pintype "passive"))
      (node (ref "C82") (pin "1") (pinfunction "1_1") (pintype "passive"))
      (node (ref "C83") (pin "2") (pintype "passive"))
      (node (ref "C84") (pin "1") (pinfunction "1_1") (pintype "passive"))
      (node (ref "C85") (pin "2") (pinfunction "2_2") (pintype "passive"))
      (node (ref "C86") (pin "2") (pinfunction "2_2") (pintype "passive"))
      (node (ref "C87") (pin "1") (pinfunction "1_1") (pintype "passive"))
      (node (ref "C88") (pin "2") (pinfunction "2_2") (pintype "passive"))
      (node (ref "C89") (pin "2") (pinfunction "2_2") (pintype "passive"))
      (node (ref "C90") (pin "2") (pinfunction "2_2") (pintype "passive"))
      (node (ref "C91") (pin "2") (pinfunction "2_2") (pintype "passive"))
      (node (ref "C92") (pin "2") (pinfunction "2_2") (pintype "passive"))
      (node (ref "C93") (pin "1") (pinfunction "1_1") (pintype "passive"))
      (node (ref "C94") (pin "2") (pinfunction "2_2") (pintype "passive"))
      (node (ref "C95") (pin "2") (pinfunction "2_2") (pintype "passive"))
      (node (ref "C96") (pin "2") (pinfunction "2_2") (pintype "passive"))
      (node (ref "C97") (pin "2") (pinfunction "2_2") (pintype "passive"))
      (node (ref "C98") (pin "2") (pinfunction "2_2") (pintype "passive"))
      (node (ref "C99") (pin "2") (pinfunction "2_2") (pintype "passive"))
      (node (ref "G3") (pin "2") (pinfunction "gnd_2") (pintype "power_in"))
      (node (ref "P5") (pin "1") (pinfunction "1_1") (pintype "passive"))
      (node (ref "P5") (pin "13") (pinfunction "13_13") (pintype "passive"))
      (node (ref "P5") (pin "24") (pinfunction "24_24") (pintype "passive"))
      (node (ref "P5") (pin "25") (pinfunction "25_25") (pintype "passive"))
      (node (ref "R31") (pin "2") (pinfunction "2_2") (pintype "passive"))
      (node (ref "R32") (pin "2") (pinfunction "2_2") (pintype "passive"))
      (node (ref "R33") (pin "2") (pinfunction "2_2") (pintype "passive"))
      (node (ref "U7") (pin "A1") (pinfunction "U3VSSQ_A1") (pintype "passive"))
      (node (ref "U7") (pin "A8") (pinfunction "VSS12_A8") (pintype "passive"))
      (node (ref "U7") (pin "B2") (pinfunction "FSLC0_B2") (pintype "passive"))
      (node (ref "U7") (pin "B4") (pinfunction "FSLC1_B4") (pintype "passive"))
      (node (ref "U7") (pin "B7") (pinfunction "AVSS_B7") (pintype "passive"))
      (node (ref "U7") (pin "B8") (pinfunction "U2PLLVSSQ_B8") (pintype "passive"))
      (node (ref "U7") (pin "B9") (pinfunction "U2AFEVSSQ_B9") (pintype "passive"))
      (node (ref "U7") (pin "D8") (pinfunction "VSS5_D8") (pintype "passive"))
      (node (ref "U7") (pin "E2") (pinfunction "VSS3_E2") (pintype "passive"))
      (node (ref "U7") (pin "E6") (pinfunction "FSLC2_E6") (pintype "passive"))
      (node (ref "U7") (pin "G1") (pinfunction "VSS1_G1") (pintype "passive"))
      (node (ref "U7") (pin "G11") (pinfunction "VSS6_G11") (pintype "passive"))
      (node (ref "U7") (pin "K3") (pinfunction "VSS10_K3") (pintype "passive"))
      (node (ref "U7") (pin "K4") (pinfunction "VSS8_K4") (pintype "passive"))
      (node (ref "U7") (pin "L1") (pinfunction "VSS2_L1") (pintype "passive"))
      (node (ref "U7") (pin "L11") (pinfunction "VSS7_L11") (pintype "passive"))
      (node (ref "U7") (pin "L2") (pinfunction "VSS11_L2") (pintype "passive"))
      (node (ref "U7") (pin "L3") (pinfunction "VSS9_L3") (pintype "passive"))
      (node (ref "U7") (pin "L6") (pinfunction "VSS4_L6") (pintype "passive"))
      (node (ref "U8") (pin "4") (pinfunction "GND_4") (pintype "passive"))
      (node (ref "U9") (pin "4") (pinfunction "GND_4") (pintype "passive"))
    )
    (net (code "93") (name "Net-(P6-Pad1)") (class "Default")
      (node (ref "P6") (pin "1") (pinfunction "1_1") (pintype "passive"))
      (node (ref "R25") (pin "1") (pinfunction "1_1") (pintype "passive"))
    )
    (net (code "94") (name "Net-(U7A-PMODE0)") (class "Default")
      (node (ref "P6") (pin "2") (pinfunction "2_2") (pintype "passive"))
      (node (ref "U7") (pin "G4") (pinfunction "PMODE0_G4") (pintype "passive"))
    )
    (net (code "95") (name "Net-(U7A-PMODE1)") (class "Default")
      (node (ref "R26") (pin "1") (pinfunction "1_1") (pintype "passive"))
      (node (ref "U7") (pin "H4") (pinfunction "PMODE1_H4") (pintype "passive"))
    )
    (net (code "96") (name "Net-(U7D-R_USB2)") (class "Default")
      (node (ref "R32") (pin "1") (pinfunction "1_1") (pintype "passive"))
      (node (ref "U7") (pin "C8") (pinfunction "R_USB2_C8") (pintype "passive"))
    )
    (net (code "97") (name "Net-(U7D-R_USB3)") (class "Default")
      (node (ref "R33") (pin "1") (pinfunction "1_1") (pintype "passive"))
      (node (ref "U7") (pin "B3") (pinfunction "R_USB3_B3") (pintype "passive"))
    )
    (net (code "98") (name "Net-(U7G-CVDDQ)") (class "Default")
      (node (ref "C85") (pin "1") (pinfunction "1_1") (pintype "passive"))
      (node (ref "C86") (pin "1") (pinfunction "1_1") (pintype "passive"))
      (node (ref "L9") (pin "1") (pinfunction "1_1") (pintype "passive"))
      (node (ref "U7") (pin "B6") (pinfunction "CVDDQ_B6") (pintype "passive"))
    )
    (net (code "99") (name "Net-(V3-A)") (class "Default")
      (node (ref "R23") (pin "1") (pinfunction "1_1") (pintype "passive"))
      (node (ref "V3") (pin "1") (pinfunction "A_1") (pintype "passive"))
    )
    (net (code "100") (name "RXVDDQ") (class "Default")
      (node (ref "C119") (pin "2") (pinfunction "2_2") (pintype "passive"))
      (node (ref "C120") (pin "1") (pinfunction "1_1") (pintype "passive"))
      (node (ref "L11") (pin "2") (pinfunction "2_2") (pintype "passive"))
      (node (ref "U7") (pin "A2") (pinfunction "U3RXVDDQ_A2") (pintype "passive"))
    )
    (net (code "101") (name "TXVDDQ") (class "Default")
      (node (ref "C107") (pin "2") (pinfunction "2_2") (pintype "passive"))
      (node (ref "C108") (pin "1") (pinfunction "1_1") (pintype "passive"))
      (node (ref "L12") (pin "2") (pinfunction "2_2") (pintype "passive"))
      (node (ref "U7") (pin "B5") (pinfunction "U3TXVDDQ_B5") (pintype "passive"))
    )
    (net (code "102") (name "VCC(+3.3V)") (class "Default")
      (node (ref "C100") (pin "1") (pinfunction "1_1") (pintype "passive"))
      (node (ref "C109") (pin "1") (pintype "passive"))
      (node (ref "C110") (pin "1") (pinfunction "1_1") (pintype "passive"))
      (node (ref "C111") (pin "1") (pinfunction "1_1") (pintype "passive"))
      (node (ref "C112") (pin "1") (pinfunction "1_1") (pintype "passive"))
      (node (ref "C113") (pin "1") (pinfunction "1_1") (pintype "passive"))
      (node (ref "C114") (pin "1") (pinfunction "1_1") (pintype "passive"))
      (node (ref "C115") (pin "1") (pinfunction "1_1") (pintype "passive"))
      (node (ref "C116") (pin "1") (pinfunction "1_1") (pintype "passive"))
      (node (ref "C117") (pin "1") (pinfunction "1_1") (pintype "passive"))
      (node (ref "C83") (pin "1") (pintype "passive"))
      (node (ref "C87") (pin "2") (pinfunction "2_2") (pintype "passive"))
      (node (ref "C95") (pin "1") (pinfunction "1_1") (pintype "passive"))
      (node (ref "C96") (pin "1") (pinfunction "1_1") (pintype "passive"))
      (node (ref "C97") (pin "1") (pinfunction "1_1") (pintype "passive"))
      (node (ref "C98") (pin "1") (pinfunction "1_1") (pintype "passive"))
      (node (ref "C99") (pin "1") (pinfunction "1_1") (pintype "passive"))
      (node (ref "G3") (pin "4") (pinfunction "vcc_4") (pintype "power_in"))
      (node (ref "L9") (pin "2") (pinfunction "2_2") (pintype "passive"))
      (node (ref "P5") (pin "27") (pinfunction "27_27") (pintype "passive"))
      (node (ref "P5") (pin "28") (pinfunction "28_28") (pintype "passive"))
      (node (ref "P5") (pin "29") (pinfunction "29_29") (pintype "passive"))
      (node (ref "P5") (pin "30") (pinfunction "30_30") (pintype "passive"))
      (node (ref "R23") (pin "2") (pinfunction "2_2") (pintype "passive"))
      (node (ref "R25") (pin "2") (pinfunction "2_2") (pintype "passive"))
      (node (ref "R26") (pin "2") (pinfunction "2_2") (pintype "passive"))
      (node (ref "R27") (pin "1") (pinfunction "1_1") (pintype "passive"))
      (node (ref "R28") (pin "1") (pinfunction "1_1") (pintype "passive"))
      (node (ref "R29") (pin "2") (pinfunction "2_2") (pintype "passive"))
      (node (ref "R30") (pin "2") (pinfunction "2_2") (pintype "passive"))
      (node (ref "U7") (pin "B1") (pinfunction "VIO4_B1") (pintype "passive"))
      (node (ref "U7") (pin "C11") (pinfunction "VIO5_C11") (pintype "passive"))
      (node (ref "U7") (pin "E10") (pinfunction "VBAT_E10") (pintype "passive"))
      (node (ref "U7") (pin "E3") (pinfunction "VIO3_E3") (pintype "passive"))
      (node (ref "U7") (pin "F1") (pinfunction "VIO2_F1") (pintype "passive"))
      (node (ref "U7") (pin "H11") (pinfunction "VIO1_2_H11") (pintype "passive"))
      (node (ref "U7") (pin "L9") (pinfunction "VIO1_1_L9") (pintype "passive"))
      (node (ref "U8") (pin "8") (pinfunction "VCC_8") (pintype "passive"))
      (node (ref "U9") (pin "8") (pinfunction "VCC_8") (pintype "passive"))
    )
    (net (code "103") (name "VCC(+5V)") (class "Default")
      (node (ref "C88") (pin "1") (pinfunction "1_1") (pintype "passive"))
      (node (ref "U7") (pin "E11") (pinfunction "VBUS_E11") (pintype "passive"))
    )
    (net (code "104") (name "VDD(+1.2V)") (class "Default")
      (node (ref "C102") (pin "1") (pinfunction "1_1") (pintype "passive"))
      (node (ref "C103") (pin "1") (pinfunction "1_1") (pintype "passive"))
      (node (ref "C104") (pin "1") (pinfunction "1_1") (pintype "passive"))
      (node (ref "C105") (pin "1") (pinfunction "1_1") (pintype "passive"))
      (node (ref "C118") (pin "2") (pinfunction "2_2") (pintype "passive"))
      (node (ref "C89") (pin "1") (pinfunction "1_1") (pintype "passive"))
      (node (ref "C90") (pin "1") (pinfunction "1_1") (pintype "passive"))
      (node (ref "C91") (pin "1") (pinfunction "1_1") (pintype "passive"))
      (node (ref "C92") (pin "1") (pinfunction "1_1") (pintype "passive"))
      (node (ref "L10") (pin "1") (pinfunction "1_1") (pintype "passive"))
      (node (ref "L11") (pin "1") (pinfunction "1_1") (pintype "passive"))
      (node (ref "L12") (pin "1") (pinfunction "1_1") (pintype "passive"))
      (node (ref "U7") (pin "B10") (pinfunction "VDD8_B10") (pintype "passive"))
      (node (ref "U7") (pin "C3") (pinfunction "VDD2_C3") (pintype "passive"))
      (node (ref "U7") (pin "E9") (pinfunction "VDD4_E9") (pintype "passive"))
      (node (ref "U7") (pin "F11") (pinfunction "VDD5_F11") (pintype "passive"))
      (node (ref "U7") (pin "H1") (pinfunction "VDD1_H1") (pintype "passive"))
      (node (ref "U7") (pin "J11") (pinfunction "VDD7_J11") (pintype "passive"))
      (node (ref "U7") (pin "L5") (pinfunction "VDD6_L5") (pintype "passive"))
      (node (ref "U7") (pin "L7") (pinfunction "VDD3_L7") (pintype "passive"))
    )
    (net (code "105") (name "unconnected-(G3-ena-Pad1)") (class "Default")
      (node (ref "G3") (pin "1") (pinfunction "ena_1") (pintype "passive"))
    )
    (net (code "106") (name "unconnected-(RS9-Pad3)") (class "Default")
      (node (ref "RS9") (pin "3") (pinfunction "3_3") (pintype "bidirectional"))
    )
    (net (code "107") (name "unconnected-(RS9-Pad6)") (class "Default")
      (node (ref "RS9") (pin "6") (pinfunction "6_6") (pintype "bidirectional"))
    )
    (net (code "108") (name "unconnected-(U7A-CTL9-PadH6)") (class "Default")
      (node (ref "U7") (pin "H6") (pinfunction "CTL9_H6") (pintype "passive"))
    )
    (net (code "109") (name "unconnected-(U7A-CTL10-PadK5)") (class "Default")
      (node (ref "U7") (pin "K5") (pinfunction "CTL10_K5") (pintype "passive"))
    )
    (net (code "110") (name "unconnected-(U7A-PMODE2-PadL4)") (class "Default")
      (node (ref "U7") (pin "L4") (pinfunction "PMODE2_L4") (pintype "passive+no_connect"))
    )
    (net (code "111") (name "unconnected-(U7B-DQ16-PadK2)") (class "Default")
      (node (ref "U7") (pin "K2") (pinfunction "DQ16_K2") (pintype "passive"))
    )
    (net (code "112") (name "unconnected-(U7B-DQ17-PadJ4)") (class "Default")
      (node (ref "U7") (pin "J4") (pinfunction "DQ17_J4") (pintype "passive"))
    )
    (net (code "113") (name "unconnected-(U7B-DQ18-PadK1)") (class "Default")
      (node (ref "U7") (pin "K1") (pinfunction "DQ18_K1") (pintype "passive"))
    )
    (net (code "114") (name "unconnected-(U7B-DQ19-PadJ2)") (class "Default")
      (node (ref "U7") (pin "J2") (pinfunction "DQ19_J2") (pintype "passive"))
    )
    (net (code "115") (name "unconnected-(U7B-DQ20-PadJ3)") (class "Default")
      (node (ref "U7") (pin "J3") (pinfunction "DQ20_J3") (pintype "passive"))
    )
    (net (code "116") (name "unconnected-(U7B-DQ21-PadJ1)") (class "Default")
      (node (ref "U7") (pin "J1") (pinfunction "DQ21_J1") (pintype "passive"))
    )
    (net (code "117") (name "unconnected-(U7B-DQ22-PadH2)") (class "Default")
      (node (ref "U7") (pin "H2") (pinfunction "DQ22_H2") (pintype "passive"))
    )
    (net (code "118") (name "unconnected-(U7B-DQ23-PadH3)") (class "Default")
      (node (ref "U7") (pin "H3") (pinfunction "DQ23_H3") (pintype "passive"))
    )
    (net (code "119") (name "unconnected-(U7B-DQ24-PadF4)") (class "Default")
      (node (ref "U7") (pin "F4") (pinfunction "DQ24_F4") (pintype "passive"))
    )
    (net (code "120") (name "unconnected-(U7B-DQ25-PadG2)") (class "Default")
      (node (ref "U7") (pin "G2") (pinfunction "DQ25_G2") (pintype "passive"))
    )
    (net (code "121") (name "unconnected-(U7B-DQ26-PadG3)") (class "Default")
      (node (ref "U7") (pin "G3") (pinfunction "DQ26_G3") (pintype "passive"))
    )
    (net (code "122") (name "unconnected-(U7B-DQ27-PadF3)") (class "Default")
      (node (ref "U7") (pin "F3") (pinfunction "DQ27_F3") (pintype "passive"))
    )
    (net (code "123") (name "unconnected-(U7B-GPIO45-PadF2)") (class "Default")
      (node (ref "U7") (pin "F2") (pinfunction "GPIO45_F2") (pintype "passive"))
    )
    (net (code "124") (name "unconnected-(U7C-DQ28-PadF5)") (class "Default")
      (node (ref "U7") (pin "F5") (pinfunction "DQ28_F5") (pintype "passive"))
    )
    (net (code "125") (name "unconnected-(U7C-DQ29-PadE1)") (class "Default")
      (node (ref "U7") (pin "E1") (pinfunction "DQ29_E1") (pintype "passive"))
    )
    (net (code "126") (name "unconnected-(U7C-DQ30-PadE5)") (class "Default")
      (node (ref "U7") (pin "E5") (pinfunction "DQ30_E5") (pintype "passive"))
    )
    (net (code "127") (name "unconnected-(U7C-DQ31-PadE4)") (class "Default")
      (node (ref "U7") (pin "E4") (pinfunction "DQ31_E4") (pintype "passive"))
    )
    (net (code "128") (name "unconnected-(U7C-I2S-CLK-PadD1)") (class "Default")
      (node (ref "U7") (pin "D1") (pinfunction "I2S-CLK_D1") (pintype "passive"))
    )
    (net (code "129") (name "unconnected-(U7C-I2S-MCLK-PadC4)") (class "Default")
      (node (ref "U7") (pin "C4") (pinfunction "I2S-MCLK_C4") (pintype "passive"))
    )
    (net (code "130") (name "unconnected-(U7C-I2S-SD-PadD2)") (class "Default")
      (node (ref "U7") (pin "D2") (pinfunction "I2S-SD_D2") (pintype "passive"))
    )
    (net (code "131") (name "unconnected-(U7C-I2S-WS-PadD3)") (class "Default")
      (node (ref "U7") (pin "D3") (pinfunction "I2S-WS_D3") (pintype "passive"))
    )
    (net (code "132") (name "unconnected-(U7D-NC-PadA11)") (class "Default")
      (node (ref "U7") (pin "A11") (pinfunction "NC_A11") (pintype "passive"))
    )
    (net (code "133") (name "unconnected-(U7E-CLKIN-PadD7)") (class "Default")
      (node (ref "U7") (pin "D7") (pinfunction "CLKIN_D7") (pintype "passive"))
    )
    (net (code "134") (name "unconnected-(U7F-TCK-PadF6)") (class "Default")
      (node (ref "U7") (pin "F6") (pinfunction "TCK_F6") (pintype "passive"))
    )
    (net (code "135") (name "unconnected-(U7F-TDI-PadE7)") (class "Default")
      (node (ref "U7") (pin "E7") (pinfunction "TDI_E7") (pintype "passive"))
    )
    (net (code "136") (name "unconnected-(U7F-TDO-PadC10)") (class "Default")
      (node (ref "U7") (pin "C10") (pinfunction "TDO_C10") (pintype "passive"))
    )
    (net (code "137") (name "unconnected-(U7F-TMS-PadE8)") (class "Default")
      (node (ref "U7") (pin "E8") (pinfunction "TMS_E8") (pintype "passive"))
    )
    (net (code "138") (name "unconnected-(U7F-TRST_N-PadB11)") (class "Default")
      (node (ref "U7") (pin "B11") (pinfunction "TRST_N_B11") (pintype "passive"))
    )
    (net (code "139") (name "unconnected-(U7H-I2C-GPIO60_CHARGER-DETECT-PadD11)") (class "Default")
      (node (ref "U7") (pin "D11") (pinfunction "I2C-GPIO60_CHARGER-DETECT_D11") (pintype "passive+no_connect"))
    )
    (net (code "140") (name "unconnected-(U8-DU1-Pad1)") (class "Default")
      (node (ref "U8") (pin "1") (pinfunction "DU1_1") (pintype "passive"))
    )
    (net (code "141") (name "unconnected-(U8-DU2-Pad2)") (class "Default")
      (node (ref "U8") (pin "2") (pinfunction "DU2_2") (pintype "passive"))
    )
    (net (code "142") (name "unconnected-(U8-E2-Pad3)") (class "Default")
      (node (ref "U8") (pin "3") (pinfunction "E2_3") (pintype "passive"))
    )
    (net (code "143") (name "unconnected-(U8-~{WC}-Pad7)") (class "Default")
      (node (ref "U8") (pin "7") (pinfunction "~{WC}_7") (pintype "passive"))
    )
    (net (code "144") (name "unconnected-(U9-NC-Pad1)") (class "Default")
      (node (ref "U9") (pin "1") (pinfunction "NC_1") (pintype "passive"))
    )
    (net (code "145") (name "unconnected-(U9-NC-Pad2)") (class "Default")
      (node (ref "U9") (pin "2") (pinfunction "NC_2") (pintype "passive"))
    )
    (net (code "146") (name "unconnected-(U9-NC-Pad3)") (class "Default")
      (node (ref "U9") (pin "3") (pinfunction "NC_3") (pintype "passive"))
    )
    (net (code "147") (name "unconnected-(U9-NC-Pad7)") (class "Default")
      (node (ref "U9") (pin "7") (pinfunction "NC_7") (pintype "passive"))
    )
  )
)
